# DRV8301.net
KiCad netlist of a schematic drawn in Altium Designer
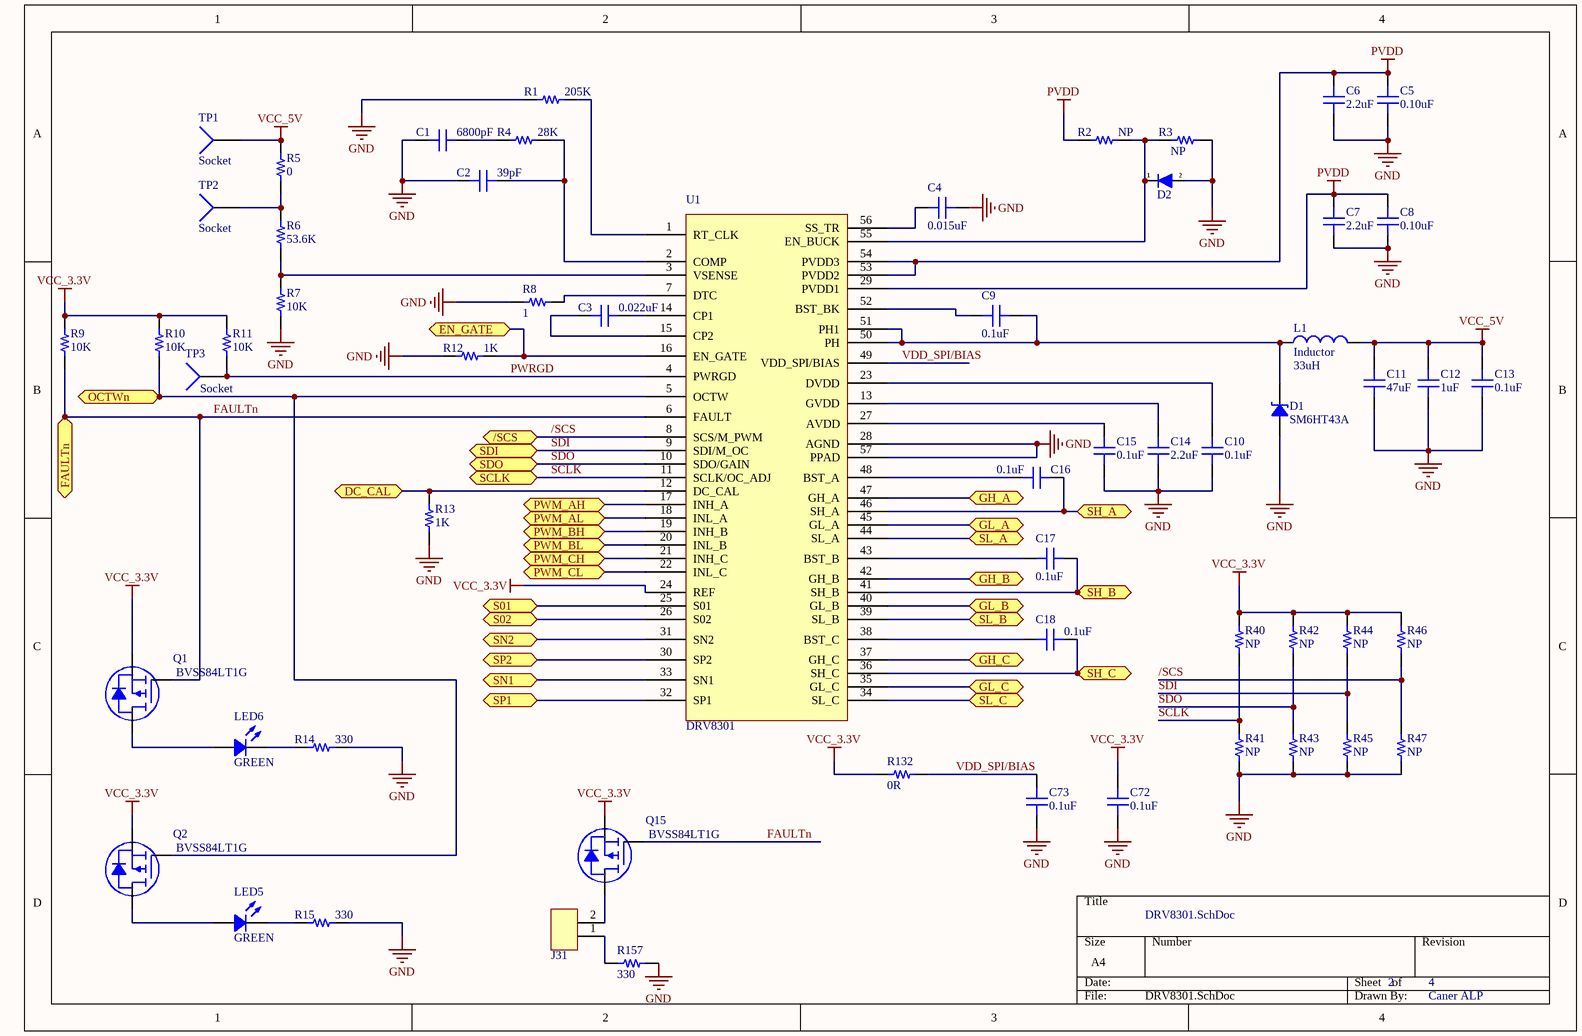
[diagram p0: DRV8301.SchDoc]

(export (version "E")
  (design (tool "Eeschema 10.0.6"))
  (components
    (comp (ref "C1")
      (value "6800pF")
      (footprint "CAP 0603/1608")
      (description "CAP CER 0.1UF 16V X7R 0603")
      (fields (field (name "PART NUMBER") "CC0603KPX7R7BB104") (field (name "MANUFACTURER") "Yageo"))
      (libsource (lib "Celestial Library Database") (part "Capacitor"))
    )
    (comp (ref "C2")
      (value "39pF")
      (footprint "CAP 0603/1608")
      (description "CAP CER 0.1UF 16V X7R 0603")
      (fields (field (name "PART NUMBER") "CC0603KPX7R7BB104") (field (name "MANUFACTURER") "Yageo"))
      (libsource (lib "Celestial Library Database") (part "Capacitor"))
    )
    (comp (ref "C3")
      (value "0.022uF")
      (footprint "CAP 0603/1608")
      (description "CAP CER 0.1UF 16V X7R 0603")
      (fields (field (name "PART NUMBER") "CC0603KPX7R7BB104") (field (name "MANUFACTURER") "Yageo"))
      (libsource (lib "Celestial Library Database") (part "Capacitor"))
    )
    (comp (ref "C4")
      (value "0.015uF")
      (footprint "CAP 0603/1608")
      (description "CAP CER 0.1UF 16V X7R 0603")
      (fields (field (name "PART NUMBER") "CC0603KPX7R7BB104") (field (name "MANUFACTURER") "Yageo"))
      (libsource (lib "Celestial Library Database") (part "Capacitor"))
    )
    (comp (ref "C5")
      (value "0.10uF")
      (footprint "CAP 0805/2012")
      (description "CAP CER 0.1UF 100V X7R 0805")
      (fields (field (name "PART NUMBER") "C0805C104K1RACTU") (field (name "MANUFACTURER") "Kemet"))
      (libsource (lib "Celestial Library Database") (part "Capacitor"))
    )
    (comp (ref "C6")
      (value "2.2uF")
      (footprint "CAP 1210/3225 - 2.5MM")
      (description "CAP CER 2.2UF 100V X7R 1210")
      (fields
        (field (name "PART NUMBER") "C3225X7R2A225K230AM")
        (field (name "MANUFACTURER") "TDK Corporation")
      )
      (libsource (lib "Celestial Library Database") (part "Capacitor"))
    )
    (comp (ref "C7")
      (value "2.2uF")
      (footprint "CAP 1210/3225 - 2.5MM")
      (description "CAP CER 2.2UF 100V X7R 1210")
      (fields
        (field (name "PART NUMBER") "C3225X7R2A225K230AM")
        (field (name "MANUFACTURER") "TDK Corporation")
      )
      (libsource (lib "Celestial Library Database") (part "Capacitor"))
    )
    (comp (ref "C8")
      (value "0.10uF")
      (footprint "CAP 0805/2012")
      (description "CAP CER 0.1UF 100V X7R 0805")
      (fields (field (name "PART NUMBER") "C0805C104K1RACTU") (field (name "MANUFACTURER") "Kemet"))
      (libsource (lib "Celestial Library Database") (part "Capacitor"))
    )
    (comp (ref "C9")
      (value "0.1uF")
      (footprint "CAP 0603/1608")
      (description "CAP CER 0.1UF 16V X7R 0603")
      (fields (field (name "PART NUMBER") "CC0603KPX7R7BB104") (field (name "MANUFACTURER") "Yageo"))
      (libsource (lib "Celestial Library Database") (part "Capacitor"))
    )
    (comp (ref "C10")
      (value "0.1uF")
      (footprint "CAP 0603/1608")
      (description "CAP CER 0.1UF 16V X7R 0603")
      (fields (field (name "PART NUMBER") "CC0603KPX7R7BB104") (field (name "MANUFACTURER") "Yageo"))
      (libsource (lib "Celestial Library Database") (part "Capacitor"))
    )
    (comp (ref "C11")
      (value "47uF")
      (footprint "CAP 1210/3225 - 2.5MM")
      (description "CAP CER 2.2UF 100V X7R 1210")
      (fields
        (field (name "PART NUMBER") "C3225X7R2A225K230AM")
        (field (name "MANUFACTURER") "TDK Corporation")
      )
      (libsource (lib "Celestial Library Database") (part "Capacitor"))
    )
    (comp (ref "C12")
      (value "1uF")
      (footprint "CAP 0603/1608")
      (description "CAP CER 0.1UF 16V X7R 0603")
      (fields (field (name "PART NUMBER") "CC0603KPX7R7BB104") (field (name "MANUFACTURER") "Yageo"))
      (libsource (lib "Celestial Library Database") (part "Capacitor"))
    )
    (comp (ref "C13")
      (value "0.1uF")
      (footprint "CAP 0603/1608")
      (description "CAP CER 0.1UF 16V X7R 0603")
      (fields (field (name "PART NUMBER") "CC0603KPX7R7BB104") (field (name "MANUFACTURER") "Yageo"))
      (libsource (lib "Celestial Library Database") (part "Capacitor"))
    )
    (comp (ref "C14")
      (value "2.2uF")
      (footprint "CAP 0805/2012")
      (description "CAP CER 0.1UF 100V X7R 0805")
      (fields (field (name "PART NUMBER") "C0805C104K1RACTU") (field (name "MANUFACTURER") "Kemet"))
      (libsource (lib "Celestial Library Database") (part "Capacitor"))
    )
    (comp (ref "C15")
      (value "0.1uF")
      (footprint "CAP 0603/1608")
      (description "CAP CER 0.1UF 16V X7R 0603")
      (fields (field (name "PART NUMBER") "CC0603KPX7R7BB104") (field (name "MANUFACTURER") "Yageo"))
      (libsource (lib "Celestial Library Database") (part "Capacitor"))
    )
    (comp (ref "C16")
      (value "0.1uF")
      (footprint "CAP 0603/1608")
      (description "CAP CER 0.1UF 16V X7R 0603")
      (fields (field (name "PART NUMBER") "CC0603KPX7R7BB104") (field (name "MANUFACTURER") "Yageo"))
      (libsource (lib "Celestial Library Database") (part "Capacitor"))
    )
    (comp (ref "C17")
      (value "0.1uF")
      (footprint "CAP 0603/1608")
      (description "CAP CER 0.1UF 16V X7R 0603")
      (fields (field (name "PART NUMBER") "CC0603KPX7R7BB104") (field (name "MANUFACTURER") "Yageo"))
      (libsource (lib "Celestial Library Database") (part "Capacitor"))
    )
    (comp (ref "C18")
      (value "0.1uF")
      (footprint "CAP 0603/1608")
      (description "CAP CER 0.1UF 16V X7R 0603")
      (fields (field (name "PART NUMBER") "CC0603KPX7R7BB104") (field (name "MANUFACTURER") "Yageo"))
      (libsource (lib "Celestial Library Database") (part "Capacitor"))
    )
    (comp (ref "C72")
      (value "0.1uF")
      (footprint "CAP 0603/1608")
      (description "CAP CER 0.1UF 16V X7R 0603")
      (fields (field (name "PART NUMBER") "CC0603KPX7R7BB104") (field (name "MANUFACTURER") "Yageo"))
      (libsource (lib "Celestial Library Database") (part "Capacitor"))
    )
    (comp (ref "C73")
      (value "0.1uF")
      (footprint "CAP 0603/1608")
      (description "CAP CER 0.1UF 16V X7R 0603")
      (fields (field (name "PART NUMBER") "CC0603KPX7R7BB104") (field (name "MANUFACTURER") "Yageo"))
      (libsource (lib "Celestial Library Database") (part "Capacitor"))
    )
    (comp (ref "D1")
      (value "SM6HT43A")
      (footprint "ST DO214AA SMB")
      (description "TVS DIODE 36.8VWM 59.3VC SMB")
      (fields (field (name "MANUFACTURER") "STMicroelectronics"))
      (libsource (lib "Celestial Library Database") (part "Diode Zener"))
    )
    (comp (ref "D2")
      (value "1N5819")
      (footprint "SOD-123")
      (description "DIODE SCHOTTKY 40V 1A SOD123")
      (fields
        (field (name "PART NUMBER") "DIO00002")
        (field (name "MANUFACTURER PART NUMBER") "1N5819HW-7-F")
        (field (name "CHECK FOOTPRINT") "AB")
        (field (name "CHECK SYMBOL") "AB")
      )
      (libsource (lib "open-components") (part "1N5819"))
    )
    (comp (ref "J31")
      (value "HDR_1x2")
      (footprint "PINHEAD_2.54mm_1x2")
      (description "CONN HEADER 2POS .100 VERT TIN")
      (fields (field (name "PART NUMBER") "J00093") (field (name "MANUFACTURER") "Molex, LLC"))
      (libsource (lib "open-components") (part "HDR_1x2"))
    )
    (comp (ref "L1")
      (value "Inductor")
      (footprint "9x9mm SMD Coil")
      (fields (field (name "ALTIUM_VALUE") "33uH") (field (name "PUBLISHER") "Altium Limited"))
      (libsource (lib "Miscellaneous Devices") (part "Inductor"))
    )
    (comp (ref "LED5")
      (value "GREEN")
      (footprint "LED 0805/2012 YELLOW")
      (description "LED ORANGE CLEAR 0805 SMD")
      (fields (field (name "PART NUMBER") "LTST-C170KFKT") (field (name "MANUFACTURER") "Lite-On Inc."))
      (libsource (lib "Celestial Library Database") (part "LED"))
    )
    (comp (ref "LED6")
      (value "GREEN")
      (footprint "LED 0805/2012 YELLOW")
      (description "LED ORANGE CLEAR 0805 SMD")
      (fields (field (name "PART NUMBER") "LTST-C170KFKT") (field (name "MANUFACTURER") "Lite-On Inc."))
      (libsource (lib "Celestial Library Database") (part "LED"))
    )
    (comp (ref "Q1")
      (value "BVSS84LT1G")
      (footprint "ON SEMI SOT-23-3")
      (description "MOSFET P-CH 50V 130MA SOT-23-3")
      (fields (field (name "MANUFACTURER") "ON Semiconductor"))
      (libsource (lib "Celestial Library Database") (part "ON SEMI MOSFET P-CH SOT-23-3"))
    )
    (comp (ref "Q2")
      (value "BVSS84LT1G")
      (footprint "ON SEMI SOT-23-3")
      (description "MOSFET P-CH 50V 130MA SOT-23-3")
      (fields (field (name "MANUFACTURER") "ON Semiconductor"))
      (libsource (lib "Celestial Library Database") (part "ON SEMI MOSFET P-CH SOT-23-3"))
    )
    (comp (ref "Q15")
      (value "BVSS84LT1G")
      (footprint "ON SEMI SOT-23-3")
      (description "MOSFET P-CH 50V 130MA SOT-23-3")
      (fields (field (name "MANUFACTURER") "ON Semiconductor"))
      (libsource (lib "Celestial Library Database") (part "ON SEMI MOSFET P-CH SOT-23-3"))
    )
    (comp (ref "R1")
      (value "205K")
      (footprint "RES 0603/1608")
      (description "RES SMD 330 OHM 5% 1/10W 0603")
      (fields
        (field (name "PART NUMBER") "ERJ-3GEYJ331V")
        (field (name "MANUFACTURER") "Panasonic Electronic Components")
      )
      (libsource (lib "Celestial Library Database") (part "Resistor"))
    )
    (comp (ref "R2")
      (value "NP")
      (footprint "RES 0603/1608")
      (description "RES SMD 330 OHM 5% 1/10W 0603")
      (fields
        (field (name "PART NUMBER") "ERJ-3GEYJ331V")
        (field (name "MANUFACTURER") "Panasonic Electronic Components")
      )
      (libsource (lib "Celestial Library Database") (part "Resistor"))
    )
    (comp (ref "R3")
      (value "NP")
      (footprint "RES 0603/1608")
      (description "RES SMD 330 OHM 5% 1/10W 0603")
      (fields
        (field (name "PART NUMBER") "ERJ-3GEYJ331V")
        (field (name "MANUFACTURER") "Panasonic Electronic Components")
      )
      (libsource (lib "Celestial Library Database") (part "Resistor"))
    )
    (comp (ref "R4")
      (value "28K")
      (footprint "RES 0603/1608")
      (description "RES SMD 330 OHM 5% 1/10W 0603")
      (fields
        (field (name "PART NUMBER") "ERJ-3GEYJ331V")
        (field (name "MANUFACTURER") "Panasonic Electronic Components")
      )
      (libsource (lib "Celestial Library Database") (part "Resistor"))
    )
    (comp (ref "R5")
      (value "0")
      (footprint "RES 0603/1608")
      (description "RES SMD 330 OHM 5% 1/10W 0603")
      (fields
        (field (name "PART NUMBER") "ERJ-3GEYJ331V")
        (field (name "MANUFACTURER") "Panasonic Electronic Components")
      )
      (libsource (lib "Celestial Library Database") (part "Resistor"))
    )
    (comp (ref "R6")
      (value "53.6K")
      (footprint "RES 0603/1608")
      (description "RES SMD 330 OHM 5% 1/10W 0603")
      (fields
        (field (name "PART NUMBER") "ERJ-3GEYJ331V")
        (field (name "MANUFACTURER") "Panasonic Electronic Components")
      )
      (libsource (lib "Celestial Library Database") (part "Resistor"))
    )
    (comp (ref "R7")
      (value "10K")
      (footprint "RES 0603/1608")
      (description "RES SMD 330 OHM 5% 1/10W 0603")
      (fields
        (field (name "PART NUMBER") "ERJ-3GEYJ331V")
        (field (name "MANUFACTURER") "Panasonic Electronic Components")
      )
      (libsource (lib "Celestial Library Database") (part "Resistor"))
    )
    (comp (ref "R8")
      (value "1")
      (footprint "RES 0603/1608")
      (description "RES SMD 330 OHM 5% 1/10W 0603")
      (fields
        (field (name "PART NUMBER") "ERJ-3GEYJ331V")
        (field (name "MANUFACTURER") "Panasonic Electronic Components")
      )
      (libsource (lib "Celestial Library Database") (part "Resistor"))
    )
    (comp (ref "R9")
      (value "10K")
      (footprint "RES 0603/1608")
      (description "RES SMD 330 OHM 5% 1/10W 0603")
      (fields
        (field (name "PART NUMBER") "ERJ-3GEYJ331V")
        (field (name "MANUFACTURER") "Panasonic Electronic Components")
      )
      (libsource (lib "Celestial Library Database") (part "Resistor"))
    )
    (comp (ref "R10")
      (value "10K")
      (footprint "RES 0603/1608")
      (description "RES SMD 330 OHM 5% 1/10W 0603")
      (fields
        (field (name "PART NUMBER") "ERJ-3GEYJ331V")
        (field (name "MANUFACTURER") "Panasonic Electronic Components")
      )
      (libsource (lib "Celestial Library Database") (part "Resistor"))
    )
    (comp (ref "R11")
      (value "10K")
      (footprint "RES 0603/1608")
      (description "RES SMD 330 OHM 5% 1/10W 0603")
      (fields
        (field (name "PART NUMBER") "ERJ-3GEYJ331V")
        (field (name "MANUFACTURER") "Panasonic Electronic Components")
      )
      (libsource (lib "Celestial Library Database") (part "Resistor"))
    )
    (comp (ref "R12")
      (value "1K")
      (footprint "RES 0603/1608")
      (description "RES SMD 330 OHM 5% 1/10W 0603")
      (fields
        (field (name "PART NUMBER") "ERJ-3GEYJ331V")
        (field (name "MANUFACTURER") "Panasonic Electronic Components")
      )
      (libsource (lib "Celestial Library Database") (part "Resistor"))
    )
    (comp (ref "R13")
      (value "1K")
      (footprint "RES 0603/1608")
      (description "RES SMD 330 OHM 5% 1/10W 0603")
      (fields
        (field (name "PART NUMBER") "ERJ-3GEYJ331V")
        (field (name "MANUFACTURER") "Panasonic Electronic Components")
      )
      (libsource (lib "Celestial Library Database") (part "Resistor"))
    )
    (comp (ref "R14")
      (value "330")
      (footprint "RES 0603/1608")
      (description "RES SMD 330 OHM 5% 1/10W 0603")
      (fields
        (field (name "PART NUMBER") "ERJ-3GEYJ331V")
        (field (name "MANUFACTURER") "Panasonic Electronic Components")
      )
      (libsource (lib "Celestial Library Database") (part "Resistor"))
    )
    (comp (ref "R15")
      (value "330")
      (footprint "RES 0603/1608")
      (description "RES SMD 330 OHM 5% 1/10W 0603")
      (fields
        (field (name "PART NUMBER") "ERJ-3GEYJ331V")
        (field (name "MANUFACTURER") "Panasonic Electronic Components")
      )
      (libsource (lib "Celestial Library Database") (part "Resistor"))
    )
    (comp (ref "R40")
      (value "NP")
      (footprint "RES 0603/1608")
      (description "RES SMD 330 OHM 5% 1/10W 0603")
      (fields
        (field (name "PART NUMBER") "ERJ-3GEYJ331V")
        (field (name "MANUFACTURER") "Panasonic Electronic Components")
      )
      (libsource (lib "Celestial Library Database") (part "Resistor"))
    )
    (comp (ref "R41")
      (value "NP")
      (footprint "RES 0603/1608")
      (description "RES SMD 330 OHM 5% 1/10W 0603")
      (fields
        (field (name "PART NUMBER") "ERJ-3GEYJ331V")
        (field (name "MANUFACTURER") "Panasonic Electronic Components")
      )
      (libsource (lib "Celestial Library Database") (part "Resistor"))
    )
    (comp (ref "R42")
      (value "NP")
      (footprint "RES 0603/1608")
      (description "RES SMD 330 OHM 5% 1/10W 0603")
      (fields
        (field (name "PART NUMBER") "ERJ-3GEYJ331V")
        (field (name "MANUFACTURER") "Panasonic Electronic Components")
      )
      (libsource (lib "Celestial Library Database") (part "Resistor"))
    )
    (comp (ref "R43")
      (value "NP")
      (footprint "RES 0603/1608")
      (description "RES SMD 330 OHM 5% 1/10W 0603")
      (fields
        (field (name "PART NUMBER") "ERJ-3GEYJ331V")
        (field (name "MANUFACTURER") "Panasonic Electronic Components")
      )
      (libsource (lib "Celestial Library Database") (part "Resistor"))
    )
    (comp (ref "R44")
      (value "NP")
      (footprint "RES 0603/1608")
      (description "RES SMD 330 OHM 5% 1/10W 0603")
      (fields
        (field (name "PART NUMBER") "ERJ-3GEYJ331V")
        (field (name "MANUFACTURER") "Panasonic Electronic Components")
      )
      (libsource (lib "Celestial Library Database") (part "Resistor"))
    )
    (comp (ref "R45")
      (value "NP")
      (footprint "RES 0603/1608")
      (description "RES SMD 330 OHM 5% 1/10W 0603")
      (fields
        (field (name "PART NUMBER") "ERJ-3GEYJ331V")
        (field (name "MANUFACTURER") "Panasonic Electronic Components")
      )
      (libsource (lib "Celestial Library Database") (part "Resistor"))
    )
    (comp (ref "R46")
      (value "NP")
      (footprint "RES 0603/1608")
      (description "RES SMD 330 OHM 5% 1/10W 0603")
      (fields
        (field (name "PART NUMBER") "ERJ-3GEYJ331V")
        (field (name "MANUFACTURER") "Panasonic Electronic Components")
      )
      (libsource (lib "Celestial Library Database") (part "Resistor"))
    )
    (comp (ref "R47")
      (value "NP")
      (footprint "RES 0603/1608")
      (description "RES SMD 330 OHM 5% 1/10W 0603")
      (fields
        (field (name "PART NUMBER") "ERJ-3GEYJ331V")
        (field (name "MANUFACTURER") "Panasonic Electronic Components")
      )
      (libsource (lib "Celestial Library Database") (part "Resistor"))
    )
    (comp (ref "R132")
      (value "0R")
      (footprint "RES 0603/1608")
      (description "RES SMD 330 OHM 5% 1/10W 0603")
      (fields
        (field (name "PART NUMBER") "ERJ-3GEYJ331V")
        (field (name "MANUFACTURER") "Panasonic Electronic Components")
      )
      (libsource (lib "Celestial Library Database") (part "Resistor"))
    )
    (comp (ref "R157")
      (value "330")
      (footprint "RES 0603/1608")
      (description "RES SMD 330 OHM 5% 1/10W 0603")
      (fields
        (field (name "PART NUMBER") "ERJ-3GEYJ331V")
        (field (name "MANUFACTURER") "Panasonic Electronic Components")
      )
      (libsource (lib "Celestial Library Database") (part "Resistor"))
    )
    (comp (ref "TP1")
      (value "Socket")
      (footprint "PIN1")
      (fields (field (name "PUBLISHER") "Altium Limited"))
      (libsource (lib "Miscellaneous Connectors") (part "Socket"))
    )
    (comp (ref "TP2")
      (value "Socket")
      (footprint "PIN1")
      (fields (field (name "PUBLISHER") "Altium Limited"))
      (libsource (lib "Miscellaneous Connectors") (part "Socket"))
    )
    (comp (ref "TP3")
      (value "Socket")
      (footprint "PIN1")
      (fields (field (name "PUBLISHER") "Altium Limited"))
      (libsource (lib "Miscellaneous Connectors") (part "Socket"))
    )
    (comp (ref "U1")
      (value "DRV8301")
      (footprint "HTSSOP56")
      (libsource (lib "Altium Component") (part "DRV83xx"))
    )
  )
  (nets
    (net (code "1") (name "/DC_CAL") (class "Default")
      (node (ref "R13") (pin "2") (pinfunction "2_2") (pintype "passive"))
      (node (ref "U1") (pin "12") (pinfunction "DC_CAL_12") (pintype "passive"))
    )
    (net (code "2") (name "/EN_GATE") (class "Default")
      (node (ref "R12") (pin "2") (pinfunction "2_2") (pintype "passive"))
      (node (ref "U1") (pin "16") (pinfunction "EN_GATE_16") (pintype "passive"))
    )
    (net (code "3") (name "/FAULTn") (class "Default")
      (node (ref "Q1") (pin "1") (pinfunction "G_1") (pintype "passive"))
      (node (ref "Q15") (pin "1") (pinfunction "G_1") (pintype "passive"))
      (node (ref "R9") (pin "2") (pinfunction "2_2") (pintype "passive"))
      (node (ref "U1") (pin "6") (pinfunction "FAULT_6") (pintype "passive"))
    )
    (net (code "4") (name "/GH_A") (class "Default")
      (node (ref "U1") (pin "47") (pinfunction "GH_A_47") (pintype "passive"))
    )
    (net (code "5") (name "/GH_B") (class "Default")
      (node (ref "U1") (pin "42") (pinfunction "GH_B_42") (pintype "passive"))
    )
    (net (code "6") (name "/GH_C") (class "Default")
      (node (ref "U1") (pin "37") (pinfunction "GH_C_37") (pintype "passive"))
    )
    (net (code "7") (name "/GL_A") (class "Default")
      (node (ref "U1") (pin "45") (pinfunction "GL_A_45") (pintype "passive"))
    )
    (net (code "8") (name "/GL_B") (class "Default")
      (node (ref "U1") (pin "40") (pinfunction "GL_B_40") (pintype "passive"))
    )
    (net (code "9") (name "/GL_C") (class "Default")
      (node (ref "U1") (pin "35") (pinfunction "GL_C_35") (pintype "passive"))
    )
    (net (code "10") (name "/OCTWn") (class "Default")
      (node (ref "Q2") (pin "1") (pinfunction "G_1") (pintype "passive"))
      (node (ref "R10") (pin "2") (pinfunction "2_2") (pintype "passive"))
      (node (ref "U1") (pin "5") (pinfunction "OCTW_5") (pintype "passive"))
    )
    (net (code "11") (name "/PWM_AH") (class "Default")
      (node (ref "U1") (pin "17") (pinfunction "INH_A_17") (pintype "passive"))
    )
    (net (code "12") (name "/PWM_AL") (class "Default")
      (node (ref "U1") (pin "18") (pinfunction "INL_A_18") (pintype "passive"))
    )
    (net (code "13") (name "/PWM_BH") (class "Default")
      (node (ref "U1") (pin "19") (pinfunction "INH_B_19") (pintype "passive"))
    )
    (net (code "14") (name "/PWM_BL") (class "Default")
      (node (ref "U1") (pin "20") (pinfunction "INL_B_20") (pintype "passive"))
    )
    (net (code "15") (name "/PWM_CH") (class "Default")
      (node (ref "U1") (pin "21") (pinfunction "INH_C_21") (pintype "passive"))
    )
    (net (code "16") (name "/PWM_CL") (class "Default")
      (node (ref "U1") (pin "22") (pinfunction "INL_C_22") (pintype "passive"))
    )
    (net (code "17") (name "/PWRGD") (class "Default")
      (node (ref "R11") (pin "2") (pinfunction "2_2") (pintype "passive"))
      (node (ref "TP3") (pin "1") (pinfunction "1_1") (pintype "passive"))
      (node (ref "U1") (pin "4") (pinfunction "PWRGD_4") (pintype "passive"))
    )
    (net (code "18") (name "/S01") (class "Default")
      (node (ref "U1") (pin "25") (pinfunction "S01_25") (pintype "passive"))
    )
    (net (code "19") (name "/S02") (class "Default")
      (node (ref "U1") (pin "26") (pinfunction "S02_26") (pintype "passive"))
    )
    (net (code "20") (name "/SCLK") (class "Default")
      (node (ref "R40") (pin "2") (pinfunction "2_2") (pintype "passive"))
      (node (ref "R41") (pin "1") (pinfunction "1_1") (pintype "passive"))
      (node (ref "U1") (pin "11") (pinfunction "SCLK/OC_ADJ_11") (pintype "passive"))
    )
    (net (code "21") (name "/SDI") (class "Default")
      (node (ref "R44") (pin "2") (pinfunction "2_2") (pintype "passive"))
      (node (ref "R45") (pin "1") (pinfunction "1_1") (pintype "passive"))
      (node (ref "U1") (pin "9") (pinfunction "SDI/M_OC_9") (pintype "passive"))
    )
    (net (code "22") (name "/SDO") (class "Default")
      (node (ref "R42") (pin "2") (pinfunction "2_2") (pintype "passive"))
      (node (ref "R43") (pin "1") (pinfunction "1_1") (pintype "passive"))
      (node (ref "U1") (pin "10") (pinfunction "SDO/GAIN_10") (pintype "passive"))
    )
    (net (code "23") (name "/SH_A") (class "Default")
      (node (ref "C16") (pin "1") (pinfunction "1_1") (pintype "passive"))
      (node (ref "U1") (pin "46") (pinfunction "SH_A_46") (pintype "passive"))
    )
    (net (code "24") (name "/SH_B") (class "Default")
      (node (ref "C17") (pin "1") (pinfunction "1_1") (pintype "passive"))
      (node (ref "U1") (pin "41") (pinfunction "SH_B_41") (pintype "passive"))
    )
    (net (code "25") (name "/SH_C") (class "Default")
      (node (ref "C18") (pin "1") (pinfunction "1_1") (pintype "passive"))
      (node (ref "U1") (pin "36") (pinfunction "SH_C_36") (pintype "passive"))
    )
    (net (code "26") (name "/SL_A") (class "Default")
      (node (ref "U1") (pin "44") (pinfunction "SL_A_44") (pintype "passive"))
    )
    (net (code "27") (name "/SL_B") (class "Default")
      (node (ref "U1") (pin "39") (pinfunction "SL_B_39") (pintype "passive"))
    )
    (net (code "28") (name "/SL_C") (class "Default")
      (node (ref "U1") (pin "34") (pinfunction "SL_C_34") (pintype "passive"))
    )
    (net (code "29") (name "/SN1") (class "Default")
      (node (ref "U1") (pin "33") (pinfunction "SN1_33") (pintype "passive"))
    )
    (net (code "30") (name "/SN2") (class "Default")
      (node (ref "U1") (pin "31") (pinfunction "SN2_31") (pintype "passive"))
    )
    (net (code "31") (name "/SP1") (class "Default")
      (node (ref "U1") (pin "32") (pinfunction "SP1_32") (pintype "passive"))
    )
    (net (code "32") (name "/SP2") (class "Default")
      (node (ref "U1") (pin "30") (pinfunction "SP2_30") (pintype "passive"))
    )
    (net (code "33") (name "/VDD_SPI{slash}BIAS") (class "Default")
      (node (ref "C73") (pin "2") (pinfunction "2_2") (pintype "passive"))
      (node (ref "R132") (pin "2") (pinfunction "2_2") (pintype "passive"))
      (node (ref "U1") (pin "49") (pinfunction "VDD_SPI/BIAS_49") (pintype "passive"))
    )
    (net (code "34") (name "/{slash}SCS") (class "Default")
      (node (ref "R46") (pin "2") (pinfunction "2_2") (pintype "passive"))
      (node (ref "R47") (pin "1") (pinfunction "1_1") (pintype "passive"))
      (node (ref "U1") (pin "8") (pinfunction "SCS/M_PWM_8") (pintype "passive"))
    )
    (net (code "35") (name "GND") (class "Default")
      (node (ref "C1") (pin "2") (pinfunction "2_2") (pintype "passive"))
      (node (ref "C10") (pin "1") (pinfunction "1_1") (pintype "passive"))
      (node (ref "C11") (pin "1") (pinfunction "1_1") (pintype "passive"))
      (node (ref "C12") (pin "1") (pinfunction "1_1") (pintype "passive"))
      (node (ref "C13") (pin "1") (pinfunction "1_1") (pintype "passive"))
      (node (ref "C14") (pin "1") (pinfunction "1_1") (pintype "passive"))
      (node (ref "C15") (pin "1") (pinfunction "1_1") (pintype "passive"))
      (node (ref "C2") (pin "2") (pinfunction "2_2") (pintype "passive"))
      (node (ref "C4") (pin "2") (pinfunction "2_2") (pintype "passive"))
      (node (ref "C5") (pin "1") (pinfunction "1_1") (pintype "passive"))
      (node (ref "C6") (pin "1") (pinfunction "1_1") (pintype "passive"))
      (node (ref "C7") (pin "1") (pinfunction "1_1") (pintype "passive"))
      (node (ref "C72") (pin "1") (pinfunction "1_1") (pintype "passive"))
      (node (ref "C73") (pin "1") (pinfunction "1_1") (pintype "passive"))
      (node (ref "C8") (pin "1") (pinfunction "1_1") (pintype "passive"))
      (node (ref "D1") (pin "1") (pinfunction "1_1") (pintype "passive"))
      (node (ref "D2") (pin "2") (pinfunction "2_2") (pintype "passive"))
      (node (ref "R1") (pin "2") (pinfunction "2_2") (pintype "passive"))
      (node (ref "R12") (pin "1") (pinfunction "1_1") (pintype "passive"))
      (node (ref "R13") (pin "1") (pinfunction "1_1") (pintype "passive"))
      (node (ref "R14") (pin "2") (pinfunction "2_2") (pintype "passive"))
      (node (ref "R15") (pin "2") (pinfunction "2_2") (pintype "passive"))
      (node (ref "R157") (pin "1") (pinfunction "1_1") (pintype "passive"))
      (node (ref "R3") (pin "1") (pinfunction "1_1") (pintype "passive"))
      (node (ref "R41") (pin "2") (pinfunction "2_2") (pintype "passive"))
      (node (ref "R43") (pin "2") (pinfunction "2_2") (pintype "passive"))
      (node (ref "R45") (pin "2") (pinfunction "2_2") (pintype "passive"))
      (node (ref "R47") (pin "2") (pinfunction "2_2") (pintype "passive"))
      (node (ref "R7") (pin "1") (pinfunction "1_1") (pintype "passive"))
      (node (ref "R8") (pin "2") (pinfunction "2_2") (pintype "passive"))
      (node (ref "U1") (pin "28") (pinfunction "AGND_28") (pintype "passive"))
      (node (ref "U1") (pin "57") (pinfunction "PPAD_57") (pintype "passive"))
    )
    (net (code "36") (name "Net-(C1-Pad1)") (class "Default")
      (node (ref "C1") (pin "1") (pinfunction "1_1") (pintype "passive"))
      (node (ref "R4") (pin "2") (pinfunction "2_2") (pintype "passive"))
    )
    (net (code "37") (name "Net-(J31-Pad1)") (class "Default")
      (node (ref "J31") (pin "1") (pinfunction "1_1") (pintype "passive"))
      (node (ref "R157") (pin "2") (pinfunction "2_2") (pintype "passive"))
    )
    (net (code "38") (name "Net-(LED5-Pad2)") (class "Default")
      (node (ref "LED5") (pin "2") (pinfunction "2_2") (pintype "passive"))
      (node (ref "R15") (pin "1") (pinfunction "1_1") (pintype "passive"))
    )
    (net (code "39") (name "Net-(LED6-Pad2)") (class "Default")
      (node (ref "LED6") (pin "2") (pinfunction "2_2") (pintype "passive"))
      (node (ref "R14") (pin "1") (pinfunction "1_1") (pintype "passive"))
    )
    (net (code "40") (name "Net-(Q1-D)") (class "Default")
      (node (ref "LED6") (pin "1") (pinfunction "1_1") (pintype "passive"))
      (node (ref "Q1") (pin "2") (pinfunction "D_2") (pintype "passive"))
    )
    (net (code "41") (name "Net-(Q2-D)") (class "Default")
      (node (ref "LED5") (pin "1") (pinfunction "1_1") (pintype "passive"))
      (node (ref "Q2") (pin "2") (pinfunction "D_2") (pintype "passive"))
    )
    (net (code "42") (name "Net-(Q15-D)") (class "Default")
      (node (ref "J31") (pin "2") (pinfunction "2_2") (pintype "passive"))
      (node (ref "Q15") (pin "2") (pinfunction "D_2") (pintype "passive"))
    )
    (net (code "43") (name "Net-(R5-Pad1)") (class "Default")
      (node (ref "R5") (pin "1") (pinfunction "1_1") (pintype "passive"))
      (node (ref "R6") (pin "2") (pinfunction "2_2") (pintype "passive"))
      (node (ref "TP2") (pin "1") (pinfunction "1_1") (pintype "passive"))
    )
    (net (code "44") (name "Net-(U1-AVDD)") (class "Default")
      (node (ref "C15") (pin "2") (pinfunction "2_2") (pintype "passive"))
      (node (ref "U1") (pin "27") (pinfunction "AVDD_27") (pintype "passive"))
    )
    (net (code "45") (name "Net-(U1-BST_A)") (class "Default")
      (node (ref "C16") (pin "2") (pinfunction "2_2") (pintype "passive"))
      (node (ref "U1") (pin "48") (pinfunction "BST_A_48") (pintype "passive"))
    )
    (net (code "46") (name "Net-(U1-BST_B)") (class "Default")
      (node (ref "C17") (pin "2") (pinfunction "2_2") (pintype "passive"))
      (node (ref "U1") (pin "43") (pinfunction "BST_B_43") (pintype "passive"))
    )
    (net (code "47") (name "Net-(U1-BST_BK)") (class "Default")
      (node (ref "C9") (pin "1") (pinfunction "1_1") (pintype "passive"))
      (node (ref "U1") (pin "52") (pinfunction "BST_BK_52") (pintype "passive"))
    )
    (net (code "48") (name "Net-(U1-BST_C)") (class "Default")
      (node (ref "C18") (pin "2") (pinfunction "2_2") (pintype "passive"))
      (node (ref "U1") (pin "38") (pinfunction "BST_C_38") (pintype "passive"))
    )
    (net (code "49") (name "Net-(U1-COMP)") (class "Default")
      (node (ref "C2") (pin "1") (pinfunction "1_1") (pintype "passive"))
      (node (ref "R4") (pin "1") (pinfunction "1_1") (pintype "passive"))
      (node (ref "U1") (pin "2") (pinfunction "COMP_2") (pintype "passive"))
    )
    (net (code "50") (name "Net-(U1-CP1)") (class "Default")
      (node (ref "C3") (pin "1") (pinfunction "1_1") (pintype "passive"))
      (node (ref "U1") (pin "14") (pinfunction "CP1_14") (pintype "passive"))
    )
    (net (code "51") (name "Net-(U1-CP2)") (class "Default")
      (node (ref "C3") (pin "2") (pinfunction "2_2") (pintype "passive"))
      (node (ref "U1") (pin "15") (pinfunction "CP2_15") (pintype "passive"))
    )
    (net (code "52") (name "Net-(U1-DTC)") (class "Default")
      (node (ref "R8") (pin "1") (pinfunction "1_1") (pintype "passive"))
      (node (ref "U1") (pin "7") (pinfunction "DTC_7") (pintype "passive"))
    )
    (net (code "53") (name "Net-(U1-DVDD)") (class "Default")
      (node (ref "C10") (pin "2") (pinfunction "2_2") (pintype "passive"))
      (node (ref "U1") (pin "23") (pinfunction "DVDD_23") (pintype "passive"))
    )
    (net (code "54") (name "Net-(U1-EN_BUCK)") (class "Default")
      (node (ref "D2") (pin "1") (pinfunction "1_1") (pintype "passive"))
      (node (ref "R2") (pin "1") (pinfunction "1_1") (pintype "passive"))
      (node (ref "R3") (pin "2") (pinfunction "2_2") (pintype "passive"))
      (node (ref "U1") (pin "55") (pinfunction "EN_BUCK_55") (pintype "passive"))
    )
    (net (code "55") (name "Net-(U1-GVDD)") (class "Default")
      (node (ref "C14") (pin "2") (pinfunction "2_2") (pintype "passive"))
      (node (ref "U1") (pin "13") (pinfunction "GVDD_13") (pintype "passive"))
    )
    (net (code "56") (name "Net-(U1-PH)") (class "Default")
      (node (ref "C9") (pin "2") (pinfunction "2_2") (pintype "passive"))
      (node (ref "D1") (pin "2") (pinfunction "2_2") (pintype "passive"))
      (node (ref "L1") (pin "1") (pinfunction "1_1") (pintype "passive"))
      (node (ref "U1") (pin "50") (pinfunction "PH_50") (pintype "passive"))
      (node (ref "U1") (pin "51") (pinfunction "PH1_51") (pintype "passive"))
    )
    (net (code "57") (name "Net-(U1-RT_CLK)") (class "Default")
      (node (ref "R1") (pin "1") (pinfunction "1_1") (pintype "passive"))
      (node (ref "U1") (pin "1") (pinfunction "RT_CLK_1") (pintype "passive"))
    )
    (net (code "58") (name "Net-(U1-SS_TR)") (class "Default")
      (node (ref "C4") (pin "1") (pinfunction "1_1") (pintype "passive"))
      (node (ref "U1") (pin "56") (pinfunction "SS_TR_56") (pintype "passive"))
    )
    (net (code "59") (name "Net-(U1-VSENSE)") (class "Default")
      (node (ref "R6") (pin "1") (pinfunction "1_1") (pintype "passive"))
      (node (ref "R7") (pin "2") (pinfunction "2_2") (pintype "passive"))
      (node (ref "U1") (pin "3") (pinfunction "VSENSE_3") (pintype "passive"))
    )
    (net (code "60") (name "PVDD") (class "Default")
      (node (ref "C5") (pin "2") (pinfunction "2_2") (pintype "passive"))
      (node (ref "C6") (pin "2") (pinfunction "2_2") (pintype "passive"))
      (node (ref "C7") (pin "2") (pinfunction "2_2") (pintype "passive"))
      (node (ref "C8") (pin "2") (pinfunction "2_2") (pintype "passive"))
      (node (ref "R2") (pin "2") (pinfunction "2_2") (pintype "passive"))
      (node (ref "U1") (pin "29") (pinfunction "PVDD1_29") (pintype "passive"))
      (node (ref "U1") (pin "53") (pinfunction "PVDD2_53") (pintype "passive"))
      (node (ref "U1") (pin "54") (pinfunction "PVDD3_54") (pintype "passive"))
    )
    (net (code "61") (name "VCC_3.3V") (class "Default")
      (node (ref "C72") (pin "2") (pinfunction "2_2") (pintype "passive"))
      (node (ref "Q1") (pin "3") (pinfunction "S_3") (pintype "passive"))
      (node (ref "Q15") (pin "3") (pinfunction "S_3") (pintype "passive"))
      (node (ref "Q2") (pin "3") (pinfunction "S_3") (pintype "passive"))
      (node (ref "R10") (pin "1") (pinfunction "1_1") (pintype "passive"))
      (node (ref "R11") (pin "1") (pinfunction "1_1") (pintype "passive"))
      (node (ref "R132") (pin "1") (pinfunction "1_1") (pintype "passive"))
      (node (ref "R40") (pin "1") (pinfunction "1_1") (pintype "passive"))
      (node (ref "R42") (pin "1") (pinfunction "1_1") (pintype "passive"))
      (node (ref "R44") (pin "1") (pinfunction "1_1") (pintype "passive"))
      (node (ref "R46") (pin "1") (pinfunction "1_1") (pintype "passive"))
      (node (ref "R9") (pin "1") (pinfunction "1_1") (pintype "passive"))
      (node (ref "U1") (pin "24") (pinfunction "REF_24") (pintype "passive"))
    )
    (net (code "62") (name "VCC_5V") (class "Default")
      (node (ref "C11") (pin "2") (pinfunction "2_2") (pintype "passive"))
      (node (ref "C12") (pin "2") (pinfunction "2_2") (pintype "passive"))
      (node (ref "C13") (pin "2") (pinfunction "2_2") (pintype "passive"))
      (node (ref "L1") (pin "2") (pinfunction "2_2") (pintype "passive"))
      (node (ref "R5") (pin "2") (pinfunction "2_2") (pintype "passive"))
      (node (ref "TP1") (pin "1") (pinfunction "1_1") (pintype "passive"))
    )
  )
)
